# ID2.net
KiCad netlist of a schematic drawn in Altium Designer
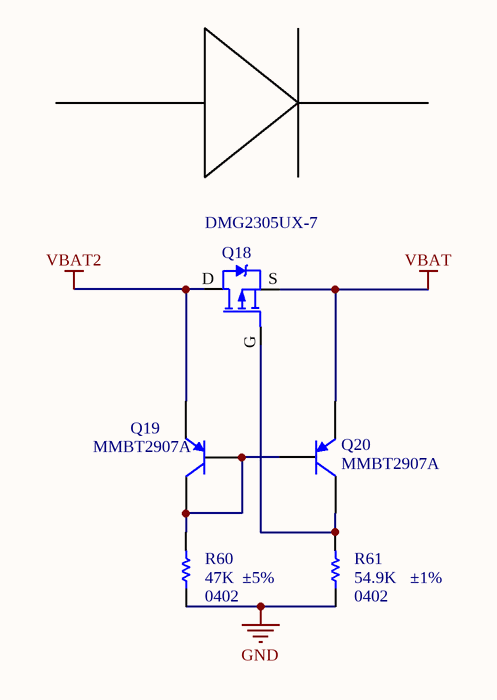
[diagram p0: ID2.SchDoc]

(export (version "E")
  (design (tool "Eeschema 10.0.6"))
  (components
    (comp (ref "Q18")
      (value "DMG2305UX")
      (footprint "DMG2305UX-7")
      (description "MOSFET P-CH 20V 4.2A SOT23")
      (fields
        (field (name "MANUFACTURER") "Diodes Incorporated")
        (field (name "MANUFACTURER PART NUMBER") "DMG2305UX-7")
        (field (name "CREATOR") "osman")
      )
      (libsource (lib "OLogic-Trans-Drivers") (part "DMG2305UX"))
    )
    (comp (ref "Q19")
      (value "MMBT2907A")
      (footprint "SOT23")
      (description "PNP General Purpose Amplifier")
      (fields (field (name "MANUFACTURER") "Fairchild Semiconductor"))
      (libsource (lib "OLogic-Trans-Drivers") (part "MMBT2907A"))
    )
    (comp (ref "Q20")
      (value "MMBT2907A")
      (footprint "SOT23")
      (description "PNP General Purpose Amplifier")
      (fields (field (name "MANUFACTURER") "Fairchild Semiconductor"))
      (libsource (lib "OLogic-Trans-Drivers") (part "MMBT2907A"))
    )
    (comp (ref "R60")
      (value "47K")
      (footprint "RESC0402(1005)_N")
      (description "47K 0402")
      (fields
        (field (name "MANUFACTURER") "Panasonic Electronic Components")
        (field (name "MANUFACTURER PART NUMBER") "ERJ-2GEJ473X")
        (field (name "TOLERANCE") "±5%")
        (field (name "SUPPLIER DEVICE PACKAGE") "0402")
      )
      (libsource (lib "OLogic-Passive") (part "RES 47K OHM 5% 1/10W 0402"))
    )
    (comp (ref "R61")
      (value "54.9K")
      (footprint "RESC0402(1005)_N")
      (description "54.9K 1% 0402")
      (fields
        (field (name "MANUFACTURER") "Panasonic Electronic Components")
        (field (name "MANUFACTURER PART NUMBER") "ERJ-2RKF5492X")
        (field (name "TOLERANCE") "±1%")
        (field (name "SUPPLIER DEVICE PACKAGE") "0402")
      )
      (libsource (lib "OLogic-Passive") (part "RES 54.9K OHM 1% 1/10W 0402"))
    )
  )
  (nets
    (net (code "1") (name "GND") (class "Default")
      (node (ref "R60") (pin "1") (pinfunction "1_1") (pintype "passive"))
      (node (ref "R61") (pin "1") (pinfunction "1_1") (pintype "passive"))
    )
    (net (code "2") (name "Net-(Q19-B)") (class "Default")
      (node (ref "Q19") (pin "1") (pinfunction "B_1") (pintype "passive"))
      (node (ref "Q19") (pin "3") (pinfunction "C_3") (pintype "passive"))
      (node (ref "Q20") (pin "1") (pinfunction "B_1") (pintype "passive"))
      (node (ref "R60") (pin "2") (pinfunction "2_2") (pintype "passive"))
    )
    (net (code "3") (name "Net-(Q20-C)") (class "Default")
      (node (ref "Q18") (pin "G") (pinfunction "G_G") (pintype "passive"))
      (node (ref "Q20") (pin "3") (pinfunction "C_3") (pintype "passive"))
      (node (ref "R61") (pin "2") (pinfunction "2_2") (pintype "passive"))
    )
    (net (code "4") (name "VBAT") (class "Default")
      (node (ref "Q18") (pin "S") (pinfunction "S_S") (pintype "passive"))
      (node (ref "Q20") (pin "2") (pinfunction "E_2") (pintype "passive"))
    )
    (net (code "5") (name "VBAT2") (class "Default")
      (node (ref "Q18") (pin "D") (pinfunction "D_D") (pintype "passive"))
      (node (ref "Q19") (pin "2") (pinfunction "E_2") (pintype "passive"))
    )
  )
)
